# DRIVER.net
KiCad netlist of a schematic drawn in Altium Designer
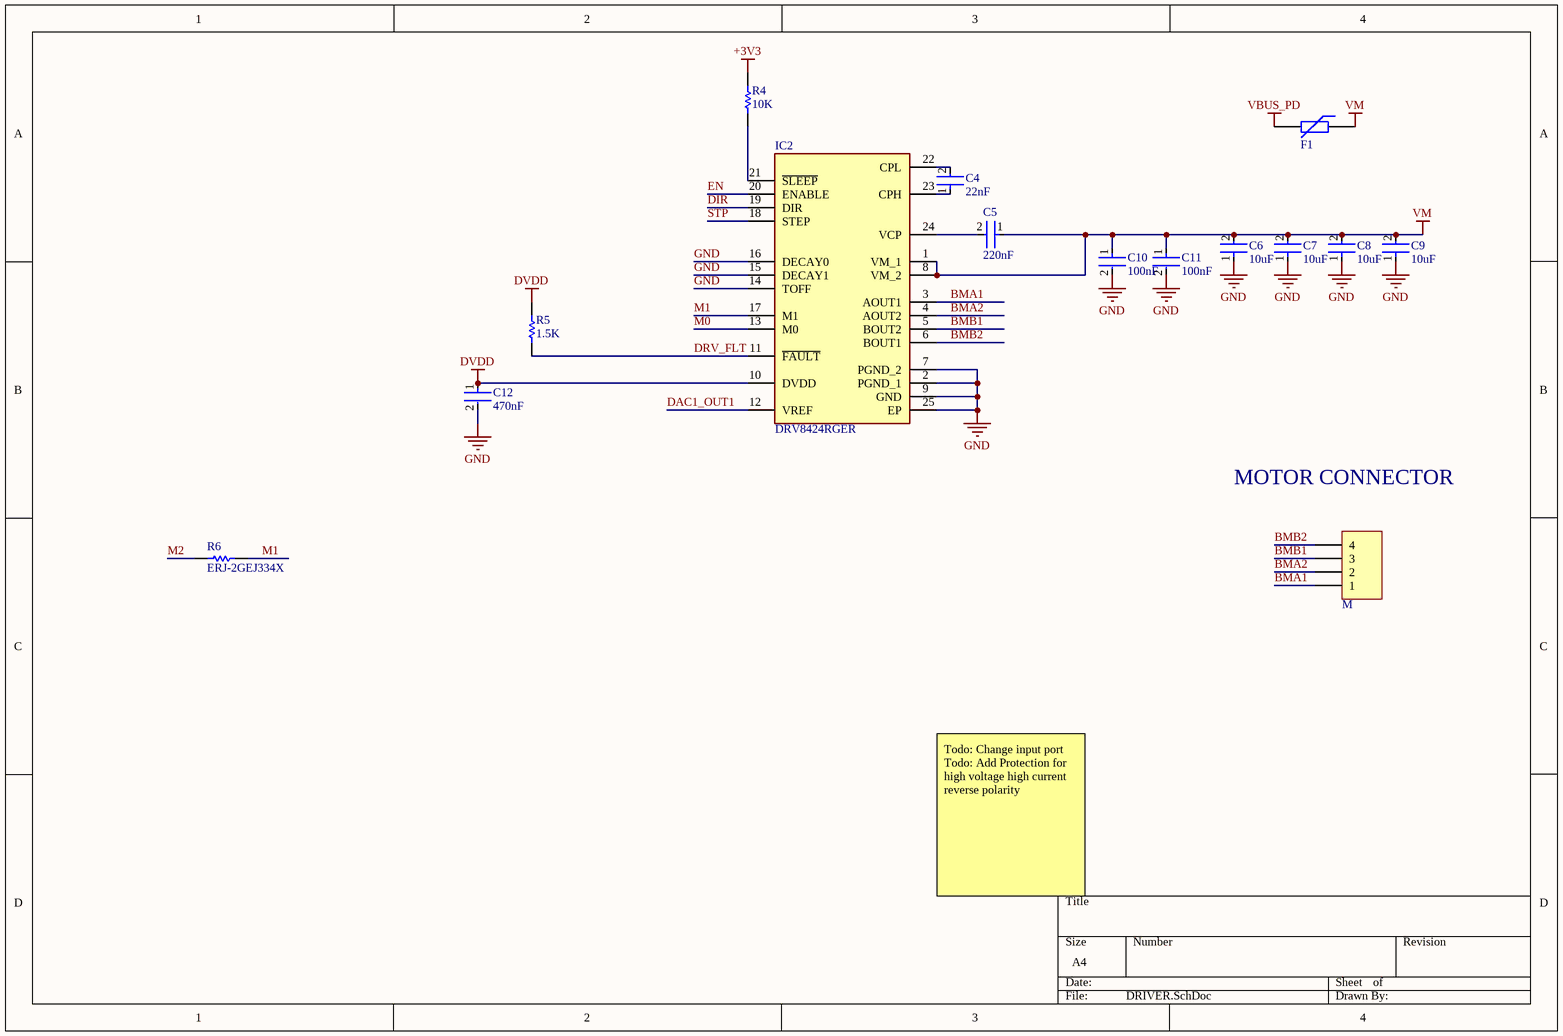
[diagram p0: DRIVER.SchDoc]

(export (version "E")
  (design (tool "Eeschema 10.0.6"))
  (components
    (comp (ref "C4")
      (value "C1005X7R1H223K050BB")
      (footprint "FP-C1005-050-0_05-IPC_C")
      (description "Multilayer Ceramic Capacitors 22nF ±10% 50V X7R SMD 0402")
      (fields (field (name "CAPACITANCE") "22nF") (field (name "TOLERANCE") "10%"))
      (libsource (lib "Altium Content Vault") (part "b4654b650e69147ec39a6b967a45e02"))
    )
    (comp (ref "C5")
      (value "C1005X7R1V224K050BC")
      (footprint "FP-C1005-050-0_05-IPC_B")
      (description "Multilayer Ceramic Capacitors 220nF ±10% 35V X7R SMD 0402")
      (fields (field (name "CAPACITANCE") "220nF") (field (name "TOLERANCE") "10%"))
      (libsource (lib "Altium Content Vault") (part "b4654b650e69147ec39a6b967a45e02"))
    )
    (comp (ref "C6")
      (value "C2012X5R1V106K125AC")
      (footprint "FP-C2012-125-0_2-IPC_B")
      (description "Multilayer Ceramic Capacitors 10μF ±10% 35V X5R SMD 0805")
      (fields (field (name "TOLERANCE") "10%") (field (name "CAPACITANCE") "10uF"))
      (libsource (lib "Altium Content Vault") (part "b4654b650e69147ec39a6b967a45e02"))
    )
    (comp (ref "C7")
      (value "C2012X5R1V106K125AC")
      (footprint "FP-C2012-125-0_2-IPC_B")
      (description "Multilayer Ceramic Capacitors 10μF ±10% 35V X5R SMD 0805")
      (fields (field (name "TOLERANCE") "10%") (field (name "CAPACITANCE") "10uF"))
      (libsource (lib "Altium Content Vault") (part "b4654b650e69147ec39a6b967a45e02"))
    )
    (comp (ref "C8")
      (value "C2012X5R1V106K125AC")
      (footprint "FP-C2012-125-0_2-IPC_B")
      (description "Multilayer Ceramic Capacitors 10μF ±10% 35V X5R SMD 0805")
      (fields (field (name "TOLERANCE") "10%") (field (name "CAPACITANCE") "10uF"))
      (libsource (lib "Altium Content Vault") (part "b4654b650e69147ec39a6b967a45e02"))
    )
    (comp (ref "C9")
      (value "C2012X5R1V106K125AC")
      (footprint "FP-C2012-125-0_2-IPC_B")
      (description "Multilayer Ceramic Capacitors 10μF ±10% 35V X5R SMD 0805")
      (fields (field (name "TOLERANCE") "10%") (field (name "CAPACITANCE") "10uF"))
      (libsource (lib "Altium Content Vault") (part "b4654b650e69147ec39a6b967a45e02"))
    )
    (comp (ref "C10")
      (value "C1005X7R1H104K050BB")
      (footprint "FP-C1005-050-0_05-IPC_C")
      (description "Multilayer Ceramic Capacitors 100nF ±10% 50V X7R SMD 0402")
      (fields
        (field (name "VOLTAGE") "50V")
        (field (name "CAPACITANCE") "100nF")
        (field (name "TOLERANCE") "10%")
      )
      (libsource (lib "Altium Content Vault") (part "b4654b650e69147ec39a6b967a45e02"))
    )
    (comp (ref "C11")
      (value "C1005X7R1H104K050BB")
      (footprint "FP-C1005-050-0_05-IPC_C")
      (description "Multilayer Ceramic Capacitors 100nF ±10% 50V X7R SMD 0402")
      (fields
        (field (name "VOLTAGE") "50V")
        (field (name "CAPACITANCE") "100nF")
        (field (name "TOLERANCE") "10%")
      )
      (libsource (lib "Altium Content Vault") (part "b4654b650e69147ec39a6b967a45e02"))
    )
    (comp (ref "C12")
      (value "C1005X5R1V474K050BC")
      (footprint "FP-C1005-050-0_05-IPC_B")
      (description "Multilayer Ceramic Capacitors 470nF ±10% 35V X5R SMD 0402")
      (fields (field (name "TOLERANCE") "10%") (field (name "CAPACITANCE") "470nF"))
      (libsource (lib "Altium Content Vault") (part "b4654b650e69147ec39a6b967a45e02"))
    )
    (comp (ref "F1")
      (value "~")
      (footprint "R1206")
      (description "PTC")
      (libsource (lib "ParsaLibrary") (part "PTC"))
    )
    (comp (ref "IC2")
      (value "DRV8424RGER")
      (footprint "SamacSys:QFN50P400X400X100-25N-D")
      (description "Integrated Circuit")
      (fields (field (name "MOUSER PART NUMBER") "595-DRV8424RGER"))
      (libsource (lib "SamacSys") (part "DRV8424RGER"))
    )
    (comp (ref "M") (value "CONN-4") (footprint "XH-4") (libsource (lib "ParsaLibrary") (part "CONN-4")))
    (comp (ref "R4")
      (value "ERJ-2GEJ103X")
      (footprint "RESC1005X40X25ML05T05")
      (fields (field (name "MANUFACTURER") "Panasonic") (field (name "RESISTANCE") "10K"))
      (libsource (lib "Altium Content Vault") (part "RES"))
    )
    (comp (ref "R5")
      (value "ERJ-2GEJ152X")
      (footprint "RESC1005X40X25NL05T05")
      (fields (field (name "MANUFACTURER") "Panasonic") (field (name "RESISTANCE") "1.5K"))
      (libsource (lib "Altium Content Vault") (part "RES"))
    )
    (comp (ref "R6")
      (value "ERJ-2GEJ334X")
      (footprint "RESC1005X40X25ML05T05")
      (fields (field (name "MANUFACTURER") "Panasonic"))
      (libsource (lib "Altium Content Vault") (part "RES"))
    )
  )
  (nets
    (net (code "1") (name "+3V3") (class "Default")
      (node (ref "R4") (pin "1") (pinfunction "1_1") (pintype "passive"))
    )
    (net (code "2") (name "/BMA1") (class "Default")
      (node (ref "IC2") (pin "3") (pinfunction "AOUT1_3") (pintype "passive"))
      (node (ref "M") (pin "1") (pinfunction "1_1") (pintype "passive"))
    )
    (net (code "3") (name "/BMA2") (class "Default")
      (node (ref "IC2") (pin "4") (pinfunction "AOUT2_4") (pintype "passive"))
      (node (ref "M") (pin "2") (pinfunction "2_2") (pintype "passive"))
    )
    (net (code "4") (name "/BMB1") (class "Default")
      (node (ref "IC2") (pin "5") (pinfunction "BOUT2_5") (pintype "passive"))
      (node (ref "M") (pin "3") (pinfunction "3_3") (pintype "passive"))
    )
    (net (code "5") (name "/BMB2") (class "Default")
      (node (ref "IC2") (pin "6") (pinfunction "BOUT1_6") (pintype "passive"))
      (node (ref "M") (pin "4") (pinfunction "4_4") (pintype "passive"))
    )
    (net (code "6") (name "/DAC1_OUT1") (class "Default")
      (node (ref "IC2") (pin "12") (pinfunction "VREF_12") (pintype "passive"))
    )
    (net (code "7") (name "/DIR") (class "Default")
      (node (ref "IC2") (pin "19") (pinfunction "DIR_19") (pintype "passive"))
    )
    (net (code "8") (name "/DRV_FLT") (class "Default")
      (node (ref "IC2") (pin "11") (pinfunction "~{FAULT}_11") (pintype "passive"))
      (node (ref "R5") (pin "2") (pinfunction "2_2") (pintype "passive"))
    )
    (net (code "9") (name "/EN") (class "Default")
      (node (ref "IC2") (pin "20") (pinfunction "ENABLE_20") (pintype "passive"))
    )
    (net (code "10") (name "/M0") (class "Default")
      (node (ref "IC2") (pin "13") (pinfunction "M0_13") (pintype "passive"))
    )
    (net (code "11") (name "/M1") (class "Default")
      (node (ref "IC2") (pin "17") (pinfunction "M1_17") (pintype "passive"))
      (node (ref "R6") (pin "2") (pinfunction "2_2") (pintype "passive"))
    )
    (net (code "12") (name "/M2") (class "Default")
      (node (ref "R6") (pin "1") (pinfunction "1_1") (pintype "passive"))
    )
    (net (code "13") (name "/STP") (class "Default")
      (node (ref "IC2") (pin "18") (pinfunction "STEP_18") (pintype "passive"))
    )
    (net (code "14") (name "DVDD") (class "Default")
      (node (ref "C12") (pin "1") (pinfunction "1_1") (pintype "passive"))
      (node (ref "IC2") (pin "10") (pinfunction "DVDD_10") (pintype "passive"))
      (node (ref "R5") (pin "1") (pinfunction "1_1") (pintype "passive"))
    )
    (net (code "15") (name "GND") (class "Default")
      (node (ref "C10") (pin "2") (pinfunction "2_2") (pintype "passive"))
      (node (ref "C11") (pin "2") (pinfunction "2_2") (pintype "passive"))
      (node (ref "C12") (pin "2") (pinfunction "2_2") (pintype "passive"))
      (node (ref "C6") (pin "1") (pinfunction "1_1") (pintype "passive"))
      (node (ref "C7") (pin "1") (pinfunction "1_1") (pintype "passive"))
      (node (ref "C8") (pin "1") (pinfunction "1_1") (pintype "passive"))
      (node (ref "C9") (pin "1") (pinfunction "1_1") (pintype "passive"))
      (node (ref "IC2") (pin "14") (pinfunction "TOFF_14") (pintype "passive"))
      (node (ref "IC2") (pin "15") (pinfunction "DECAY1_15") (pintype "passive"))
      (node (ref "IC2") (pin "16") (pinfunction "DECAY0_16") (pintype "passive"))
      (node (ref "IC2") (pin "2") (pinfunction "PGND_1_2") (pintype "passive"))
      (node (ref "IC2") (pin "25") (pinfunction "EP_25") (pintype "passive"))
      (node (ref "IC2") (pin "7") (pinfunction "PGND_2_7") (pintype "passive"))
      (node (ref "IC2") (pin "9") (pinfunction "GND_9") (pintype "passive"))
    )
    (net (code "16") (name "Net-(IC2-CPH)") (class "Default")
      (node (ref "C4") (pin "1") (pinfunction "1_1") (pintype "passive"))
      (node (ref "IC2") (pin "23") (pinfunction "CPH_23") (pintype "passive"))
    )
    (net (code "17") (name "Net-(IC2-CPL)") (class "Default")
      (node (ref "C4") (pin "2") (pinfunction "2_2") (pintype "passive"))
      (node (ref "IC2") (pin "22") (pinfunction "CPL_22") (pintype "passive"))
    )
    (net (code "18") (name "Net-(IC2-VCP)") (class "Default")
      (node (ref "C5") (pin "2") (pinfunction "2_2") (pintype "passive"))
      (node (ref "IC2") (pin "24") (pinfunction "VCP_24") (pintype "passive"))
    )
    (net (code "19") (name "Net-(IC2-~{SLEEP})") (class "Default")
      (node (ref "IC2") (pin "21") (pinfunction "~{SLEEP}_21") (pintype "passive"))
      (node (ref "R4") (pin "2") (pinfunction "2_2") (pintype "passive"))
    )
    (net (code "20") (name "VBUS_PD") (class "Default")
      (node (ref "F1") (pin "2") (pinfunction "2_2") (pintype "passive"))
    )
    (net (code "21") (name "VM") (class "Default")
      (node (ref "C10") (pin "1") (pinfunction "1_1") (pintype "passive"))
      (node (ref "C11") (pin "1") (pinfunction "1_1") (pintype "passive"))
      (node (ref "C5") (pin "1") (pinfunction "1_1") (pintype "passive"))
      (node (ref "C6") (pin "2") (pinfunction "2_2") (pintype "passive"))
      (node (ref "C7") (pin "2") (pinfunction "2_2") (pintype "passive"))
      (node (ref "C8") (pin "2") (pinfunction "2_2") (pintype "passive"))
      (node (ref "C9") (pin "2") (pinfunction "2_2") (pintype "passive"))
      (node (ref "F1") (pin "1") (pinfunction "1_1") (pintype "passive"))
      (node (ref "IC2") (pin "1") (pinfunction "VM_1_1") (pintype "passive"))
      (node (ref "IC2") (pin "8") (pinfunction "VM_2_8") (pintype "passive"))
    )
  )
)
